# AVR-TAG.net
KiCad netlist of a schematic drawn in Altium Designer
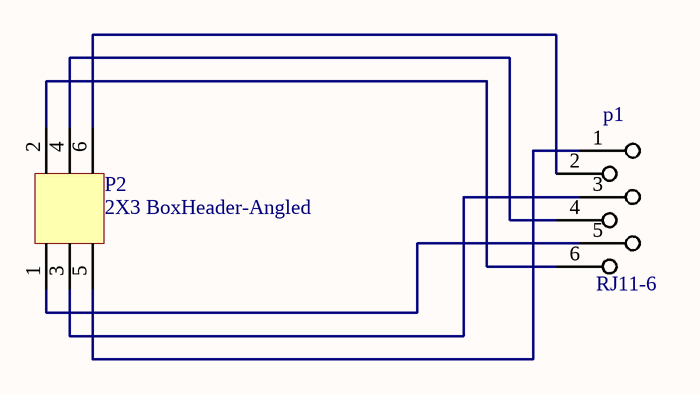
[diagram p0: AVR-TAG.SchDoc]

(export (version "E")
  (design (tool "Eeschema 10.0.6"))
  (components
    (comp (ref "p1")
      (value "RJ11-6")
      (footprint "RJ11-6pin")
      (libsource (lib "Wurth Electronic") (part "RJ11-6"))
    )
    (comp (ref "P2")
      (value "2X3 BoxHeader-Angled")
      (footprint "2X3 box header-angled")
      (libsource (lib "Wurth Electronic") (part "2X3 BoxHeader-Angled"))
    )
  )
  (nets
    (net (code "1") (name "Net-(P2-Pad1)") (class "Default")
      (node (ref "P2") (pin "1") (pinfunction "1_1") (pintype "power_in"))
      (node (ref "p1") (pin "5") (pinfunction "5_5") (pintype "passive"))
    )
    (net (code "2") (name "Net-(P2-Pad2)") (class "Default")
      (node (ref "P2") (pin "2") (pinfunction "2_2") (pintype "power_in"))
      (node (ref "p1") (pin "6") (pinfunction "6_6") (pintype "passive"))
    )
    (net (code "3") (name "Net-(P2-Pad3)") (class "Default")
      (node (ref "P2") (pin "3") (pinfunction "3_3") (pintype "power_in"))
      (node (ref "p1") (pin "3") (pinfunction "3_3") (pintype "passive"))
    )
    (net (code "4") (name "Net-(P2-Pad4)") (class "Default")
      (node (ref "P2") (pin "4") (pinfunction "4_4") (pintype "power_in"))
      (node (ref "p1") (pin "4") (pinfunction "4_4") (pintype "passive"))
    )
    (net (code "5") (name "Net-(P2-Pad5)") (class "Default")
      (node (ref "P2") (pin "5") (pinfunction "5_5") (pintype "power_in"))
      (node (ref "p1") (pin "1") (pinfunction "1_1") (pintype "passive"))
    )
    (net (code "6") (name "Net-(P2-Pad6)") (class "Default")
      (node (ref "P2") (pin "6") (pinfunction "6_6") (pintype "power_in"))
      (node (ref "p1") (pin "2") (pinfunction "2_2") (pintype "passive"))
    )
  )
)
